# doodle_with_clock2_no_fil.net
KiCad netlist of a schematic drawn in EAGLE
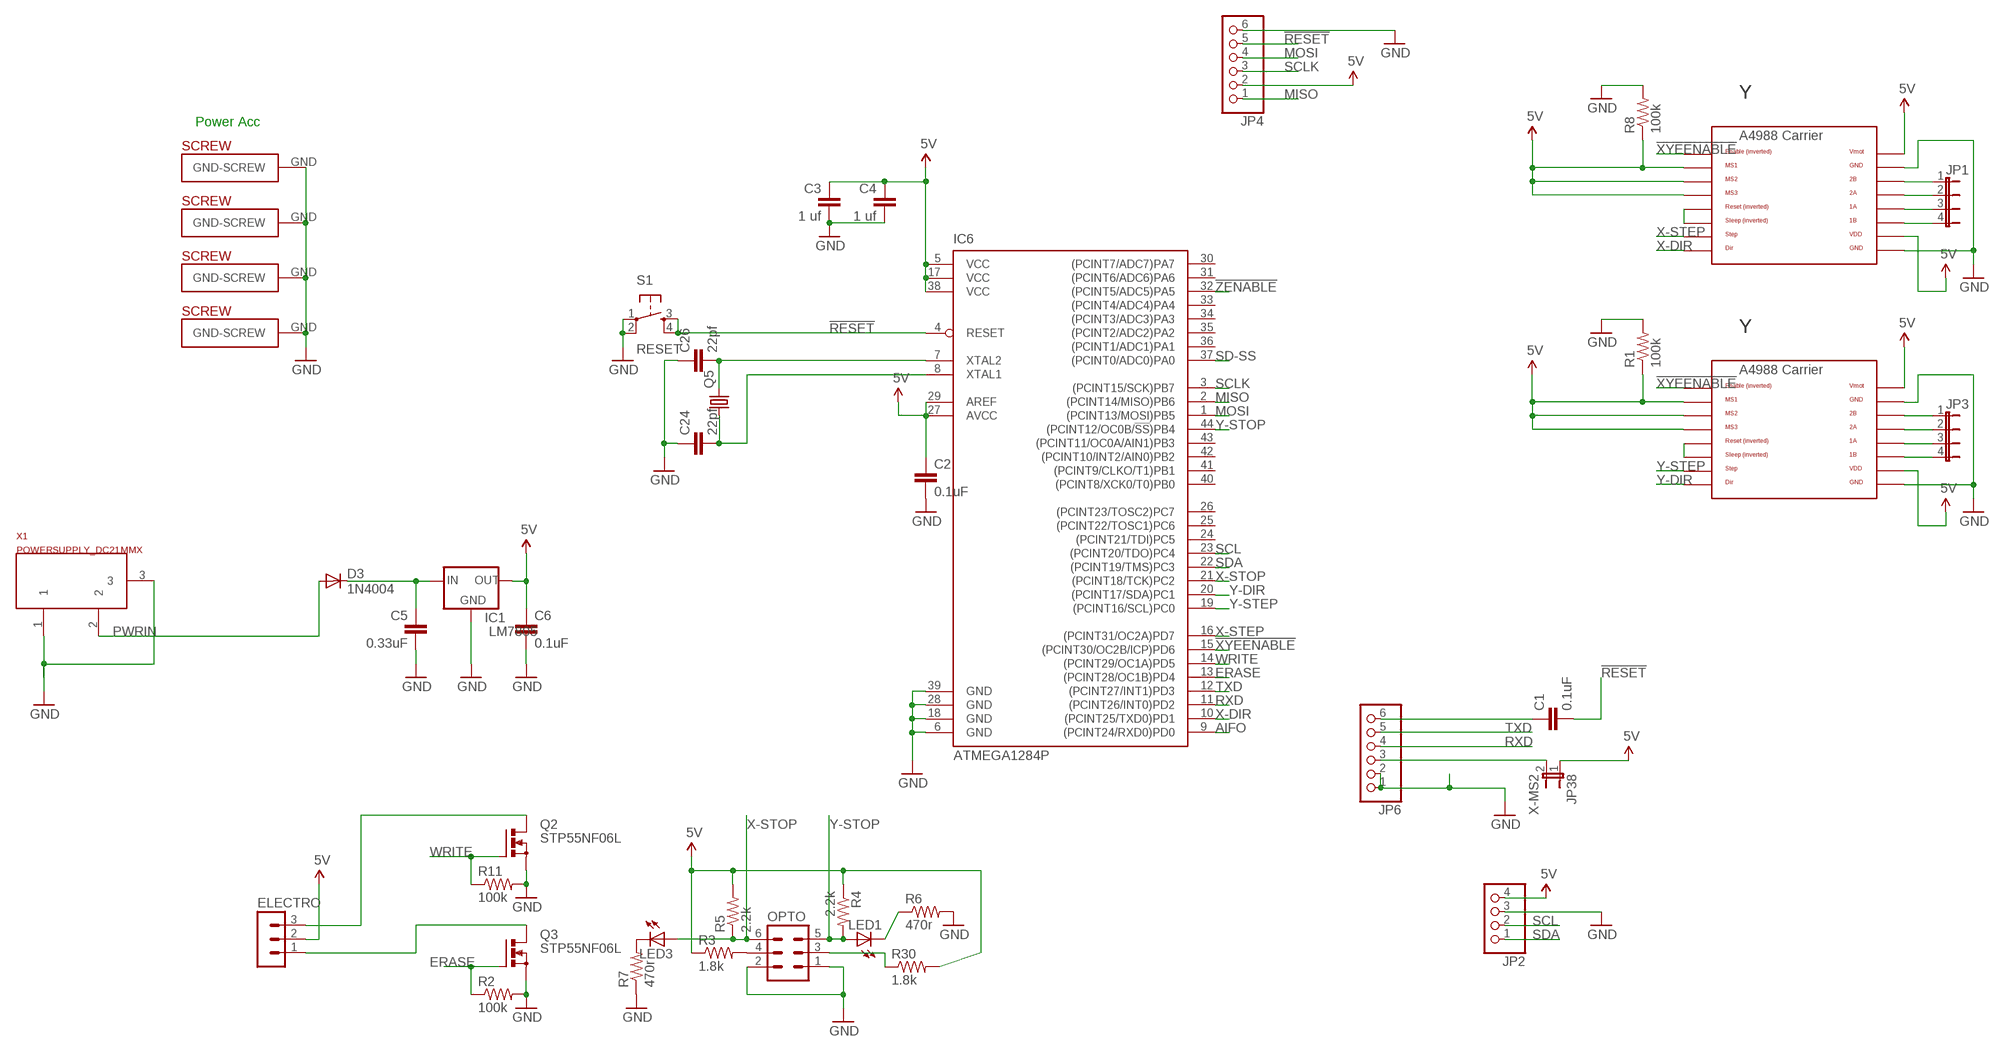
[diagram p0: schematic, sheet 1]

(export (version "E")
  (design (tool "Eeschema 10.0.6"))
  (components
    (comp (ref "C1")
      (value "0.1uF")
      (footprint "eagle-import:CAP-PTH-SMALL2")
      (libsource (lib "eagle-import") (part "CAPPTH2"))
    )
    (comp (ref "C2")
      (value "0.1uF")
      (footprint "eagle-import:CAP-PTH-SMALL2")
      (libsource (lib "eagle-import") (part "CAPPTH2"))
    )
    (comp (ref "C3")
      (value "1 uf")
      (footprint "eagle-import:CAP-PTH-SMALL2")
      (libsource (lib "eagle-import") (part "CAPPTH2"))
    )
    (comp (ref "C4")
      (value "1 uf")
      (footprint "eagle-import:CAP-PTH-SMALL2")
      (libsource (lib "eagle-import") (part "CAPPTH2"))
    )
    (comp (ref "C5")
      (value "0.33uF")
      (footprint "eagle-import:CAP-PTH-SMALL2")
      (libsource (lib "eagle-import") (part "CAPPTH2"))
    )
    (comp (ref "C6")
      (value "0.1uF")
      (footprint "eagle-import:CAP-PTH-SMALL2")
      (libsource (lib "eagle-import") (part "CAPPTH2"))
    )
    (comp (ref "C24")
      (value "22pf")
      (footprint "eagle-import:CAP-PTH-SMALL2")
      (libsource (lib "eagle-import") (part "CAPPTH2"))
    )
    (comp (ref "C26")
      (value "22pf")
      (footprint "eagle-import:CAP-PTH-SMALL2")
      (libsource (lib "eagle-import") (part "CAPPTH2"))
    )
    (comp (ref "D3")
      (value "1N4004")
      (footprint "eagle-import:DO41-10")
      (libsource (lib "eagle-import") (part "1N4004"))
    )
    (comp (ref "ELECTRO")
      (value "MA03-1")
      (footprint "eagle-import:MA03-1")
      (libsource (lib "eagle-import") (part "MA03-1"))
    )
    (comp (ref "IC1")
      (value "LM7805")
      (footprint "eagle-import:78XXL-CUSTOM")
      (libsource (lib "eagle-import") (part "V_REG_78XX"))
    )
    (comp (ref "IC6")
      (value "ATMEGA1284P")
      (footprint "eagle-import:TQFP44")
      (fields (field (name "MPN") "ATMEGA644PV-10AU"))
      (libsource (lib "eagle-import") (part "ATMEGA644A"))
    )
    (comp (ref "JP1")
      (value "JP4E")
      (footprint "eagle-import:JP4")
      (libsource (lib "eagle-import") (part "JP4E"))
    )
    (comp (ref "JP2")
      (value "PINHD-1X4")
      (footprint "eagle-import:1X04")
      (libsource (lib "eagle-import") (part "PINHD-1X4"))
    )
    (comp (ref "JP3")
      (value "JP4E")
      (footprint "eagle-import:JP4")
      (libsource (lib "eagle-import") (part "JP4E"))
    )
    (comp (ref "JP4")
      (value "PINHD-1X6/90")
      (footprint "eagle-import:1X06_90")
      (libsource (lib "eagle-import") (part "PINHD-1X6/90"))
    )
    (comp (ref "JP6")
      (value "PINHD-1X6")
      (footprint "eagle-import:1X06")
      (libsource (lib "eagle-import") (part "PINHD-1X6"))
    )
    (comp (ref "JP38")
      (value "X-MS2")
      (footprint "eagle-import:1X02")
      (libsource (lib "eagle-import") (part "JUMPER-2PTH"))
    )
    (comp (ref "LED1")
      (value "LED3MM")
      (footprint "eagle-import:LED3MM")
      (libsource (lib "eagle-import") (part "LED3MM"))
    )
    (comp (ref "LED3")
      (value "LED3MM")
      (footprint "eagle-import:LED3MM")
      (libsource (lib "eagle-import") (part "LED3MM"))
    )
    (comp (ref "OPTO")
      (value "MA03-2")
      (footprint "eagle-import:MA03-2")
      (libsource (lib "eagle-import") (part "MA03-2"))
    )
    (comp (ref "Q2")
      (value "STP55NF06L")
      (footprint "eagle-import:TO220BV")
      (libsource (lib "eagle-import") (part "IRF512"))
    )
    (comp (ref "Q3")
      (value "STP55NF06L")
      (footprint "eagle-import:TO220BV")
      (libsource (lib "eagle-import") (part "IRF512"))
    )
    (comp (ref "Q5")
      (value "CRYSTALHC49S")
      (footprint "eagle-import:HC49_S")
      (libsource (lib "eagle-import") (part "CRYSTALHC49S"))
    )
    (comp (ref "R1")
      (value "100k")
      (footprint "eagle-import:0207_7")
      (libsource (lib "eagle-import") (part "R-US_0207/7"))
    )
    (comp (ref "R2")
      (value "100k")
      (footprint "eagle-import:0207_2V")
      (libsource (lib "eagle-import") (part "resistor_R-US_0207/2V"))
    )
    (comp (ref "R3")
      (value "1.8k")
      (footprint "eagle-import:0207_2V")
      (libsource (lib "eagle-import") (part "resistor_R-US_0207/2V"))
    )
    (comp (ref "R4")
      (value "2.2k")
      (footprint "eagle-import:0207_2V")
      (libsource (lib "eagle-import") (part "resistor_R-US_0207/2V"))
    )
    (comp (ref "R5")
      (value "2.2k")
      (footprint "eagle-import:0207_2V")
      (libsource (lib "eagle-import") (part "resistor_R-US_0207/2V"))
    )
    (comp (ref "R6")
      (value "470r")
      (footprint "eagle-import:0207_2V")
      (libsource (lib "eagle-import") (part "resistor_R-US_0207/2V"))
    )
    (comp (ref "R7")
      (value "470r")
      (footprint "eagle-import:0207_2V")
      (libsource (lib "eagle-import") (part "resistor_R-US_0207/2V"))
    )
    (comp (ref "R8")
      (value "100k")
      (footprint "eagle-import:0207_7")
      (libsource (lib "eagle-import") (part "R-US_0207/7"))
    )
    (comp (ref "R11")
      (value "100k")
      (footprint "eagle-import:0207_2V")
      (libsource (lib "eagle-import") (part "resistor_R-US_0207/2V"))
    )
    (comp (ref "R30")
      (value "1.8k")
      (footprint "eagle-import:0207_2V")
      (libsource (lib "eagle-import") (part "resistor_R-US_0207/2V"))
    )
    (comp (ref "S1")
      (value "RESET")
      (footprint "eagle-import:TACTILE-PTH")
      (libsource (lib "eagle-import") (part "TAC_SWITCHPTH"))
    )
    (comp (ref "U$1")
      (value "A4988BREAKOUT")
      (footprint "eagle-import:A4988BREAKOUT")
      (libsource (lib "eagle-import") (part "A4988BREAKOUT"))
    )
    (comp (ref "U$7")
      (value "A4988BREAKOUT")
      (footprint "eagle-import:A4988BREAKOUT")
      (libsource (lib "eagle-import") (part "A4988BREAKOUT"))
    )
    (comp (ref "U$14")
      (value "PLATED-SCREW")
      (footprint "eagle-import:PLATEDSCREW")
      (libsource (lib "eagle-import") (part "PLATED-SCREW"))
    )
    (comp (ref "U$17")
      (value "PLATED-SCREW")
      (footprint "eagle-import:PLATEDSCREW")
      (libsource (lib "eagle-import") (part "PLATED-SCREW"))
    )
    (comp (ref "U$18")
      (value "PLATED-SCREW")
      (footprint "eagle-import:PLATEDSCREW")
      (libsource (lib "eagle-import") (part "PLATED-SCREW"))
    )
    (comp (ref "U$38")
      (value "PLATED-SCREW")
      (footprint "eagle-import:PLATEDSCREW")
      (libsource (lib "eagle-import") (part "PLATED-SCREW"))
    )
    (comp (ref "X1")
      (value "POWERSUPPLY_DC21MMX")
      (footprint "eagle-import:POWERSUPPLY_DC-21MM")
      (libsource (lib "eagle-import") (part "POWERSUPPLY_DC21MMX"))
    )
  )
  (nets
    (net (code "1") (name "/AIFO") (class "Default")
      (node (ref "IC6") (pin "9") (pinfunction "(PCINT24/RXD0)PD0_9") (pintype "bidirectional"))
    )
    (net (code "2") (name "/ERASE") (class "Default")
      (node (ref "IC6") (pin "13") (pinfunction "(PCINT28/OC1B)PD4_13") (pintype "bidirectional"))
      (node (ref "Q3") (pin "G") (pinfunction "G_G") (pintype "passive"))
      (node (ref "R2") (pin "1") (pinfunction "1_1") (pintype "passive"))
    )
    (net (code "3") (name "/MISO") (class "Default")
      (node (ref "IC6") (pin "2") (pinfunction "(PCINT14/MISO)PB6_2") (pintype "bidirectional"))
      (node (ref "JP4") (pin "1") (pinfunction "1_1") (pintype "passive"))
    )
    (net (code "4") (name "/MOSI") (class "Default")
      (node (ref "IC6") (pin "1") (pinfunction "(PCINT13/MOSI)PB5_1") (pintype "bidirectional"))
      (node (ref "JP4") (pin "4") (pinfunction "4_4") (pintype "passive"))
    )
    (net (code "5") (name "/PWRIN") (class "Default")
      (node (ref "D3") (pin "A") (pinfunction "A_A") (pintype "passive"))
      (node (ref "X1") (pin "2") (pinfunction "2_2") (pintype "power_in"))
    )
    (net (code "6") (name "/RXD") (class "Default")
      (node (ref "IC6") (pin "11") (pinfunction "(PCINT26/INT0)PD2_11") (pintype "bidirectional"))
      (node (ref "JP6") (pin "4") (pinfunction "4_4") (pintype "passive"))
    )
    (net (code "7") (name "/SCL") (class "Default")
      (node (ref "IC6") (pin "23") (pinfunction "(PCINT20/TDO)PC4_23") (pintype "output"))
      (node (ref "JP2") (pin "2") (pinfunction "2_2") (pintype "passive"))
    )
    (net (code "8") (name "/SCLK") (class "Default")
      (node (ref "IC6") (pin "3") (pinfunction "(PCINT15/SCK)PB7_3") (pintype "bidirectional"))
      (node (ref "JP4") (pin "3") (pinfunction "3_3") (pintype "passive"))
    )
    (net (code "9") (name "/SD-SS") (class "Default")
      (node (ref "IC6") (pin "37") (pinfunction "(PCINT0/ADC0)PA0_37") (pintype "bidirectional"))
    )
    (net (code "10") (name "/SDA") (class "Default")
      (node (ref "IC6") (pin "22") (pinfunction "(PCINT19/TMS)PC3_22") (pintype "output"))
      (node (ref "JP2") (pin "1") (pinfunction "1_1") (pintype "passive"))
    )
    (net (code "11") (name "/TXD") (class "Default")
      (node (ref "IC6") (pin "12") (pinfunction "(PCINT27/INT1)PD3_12") (pintype "bidirectional"))
      (node (ref "JP6") (pin "5") (pinfunction "5_5") (pintype "passive"))
    )
    (net (code "12") (name "/WRITE") (class "Default")
      (node (ref "IC6") (pin "14") (pinfunction "(PCINT29/OC1A)PD5_14") (pintype "bidirectional"))
      (node (ref "Q2") (pin "G") (pinfunction "G_G") (pintype "passive"))
      (node (ref "R11") (pin "1") (pinfunction "1_1") (pintype "passive"))
    )
    (net (code "13") (name "/X-DIR") (class "Default")
      (node (ref "IC6") (pin "10") (pinfunction "(PCINT25/TXD0)PD1_10") (pintype "bidirectional"))
      (node (ref "U$7") (pin "DIR") (pinfunction "DIR_DIR") (pintype "input"))
    )
    (net (code "14") (name "/X-STEP") (class "Default")
      (node (ref "IC6") (pin "16") (pinfunction "(PCINT31/OC2A)PD7_16") (pintype "bidirectional"))
      (node (ref "U$7") (pin "STEP") (pinfunction "STEP_STEP") (pintype "input"))
    )
    (net (code "15") (name "/X-STOP") (class "Default")
      (node (ref "IC6") (pin "21") (pinfunction "(PCINT18/TCK)PC2_21") (pintype "output"))
      (node (ref "LED3") (pin "A") (pinfunction "A_A") (pintype "passive"))
      (node (ref "OPTO") (pin "6") (pinfunction "6_6") (pintype "passive"))
      (node (ref "R5") (pin "1") (pinfunction "1_1") (pintype "passive"))
    )
    (net (code "16") (name "/Y-DIR") (class "Default")
      (node (ref "IC6") (pin "20") (pinfunction "(PCINT17/SDA)PC1_20") (pintype "output"))
      (node (ref "U$1") (pin "DIR") (pinfunction "DIR_DIR") (pintype "input"))
    )
    (net (code "17") (name "/Y-STEP") (class "Default")
      (node (ref "IC6") (pin "19") (pinfunction "(PCINT16/SCL)PC0_19") (pintype "output"))
      (node (ref "U$1") (pin "STEP") (pinfunction "STEP_STEP") (pintype "input"))
    )
    (net (code "18") (name "/Y-STOP") (class "Default")
      (node (ref "IC6") (pin "44") (pinfunction "(PCINT12/OC0B/~{SS})PB4_44") (pintype "bidirectional"))
      (node (ref "LED1") (pin "A") (pinfunction "A_A") (pintype "passive"))
      (node (ref "OPTO") (pin "5") (pinfunction "5_5") (pintype "passive"))
      (node (ref "R4") (pin "2") (pinfunction "2_2") (pintype "passive"))
    )
    (net (code "19") (name "/~{RESET}") (class "Default")
      (node (ref "C1") (pin "2") (pinfunction "2_2") (pintype "passive"))
      (node (ref "IC6") (pin "4") (pinfunction "RESET_4") (pintype "input"))
      (node (ref "JP4") (pin "5") (pinfunction "5_5") (pintype "passive"))
      (node (ref "S1") (pin "3") (pinfunction "3_3") (pintype "passive"))
      (node (ref "S1") (pin "4") (pinfunction "4_4") (pintype "passive"))
    )
    (net (code "20") (name "/~{XYEENABLE}") (class "Default")
      (node (ref "IC6") (pin "15") (pinfunction "(PCINT30/OC2B/ICP)PD6_15") (pintype "bidirectional"))
      (node (ref "U$1") (pin "EN") (pinfunction "EN_EN") (pintype "input"))
      (node (ref "U$7") (pin "EN") (pinfunction "EN_EN") (pintype "input"))
    )
    (net (code "21") (name "/~{ZENABLE}") (class "Default")
      (node (ref "IC6") (pin "32") (pinfunction "(PCINT5/ADC5)PA5_32") (pintype "bidirectional"))
    )
    (net (code "22") (name "5V") (class "Default")
      (node (ref "C2") (pin "1") (pinfunction "1_1") (pintype "passive"))
      (node (ref "C3") (pin "1") (pinfunction "1_1") (pintype "passive"))
      (node (ref "C4") (pin "1") (pinfunction "1_1") (pintype "passive"))
      (node (ref "C6") (pin "1") (pinfunction "1_1") (pintype "passive"))
      (node (ref "ELECTRO") (pin "2") (pinfunction "2_2") (pintype "passive"))
      (node (ref "IC1") (pin "OUT") (pinfunction "OUT_OUT") (pintype "output"))
      (node (ref "IC6") (pin "17") (pinfunction "VCC_17") (pintype "power_in"))
      (node (ref "IC6") (pin "27") (pinfunction "AVCC_27") (pintype "power_in"))
      (node (ref "IC6") (pin "29") (pinfunction "AREF_29") (pintype "passive"))
      (node (ref "IC6") (pin "38") (pinfunction "VCC_38") (pintype "power_in"))
      (node (ref "IC6") (pin "5") (pinfunction "VCC_5") (pintype "power_in"))
      (node (ref "JP2") (pin "4") (pinfunction "4_4") (pintype "passive"))
      (node (ref "JP38") (pin "1") (pinfunction "1_1") (pintype "passive"))
      (node (ref "JP4") (pin "2") (pinfunction "2_2") (pintype "passive"))
      (node (ref "R1") (pin "1") (pinfunction "1_1") (pintype "passive"))
      (node (ref "R3") (pin "1") (pinfunction "1_1") (pintype "passive"))
      (node (ref "R30") (pin "2") (pinfunction "2_2") (pintype "passive"))
      (node (ref "R4") (pin "1") (pinfunction "1_1") (pintype "passive"))
      (node (ref "R5") (pin "2") (pinfunction "2_2") (pintype "passive"))
      (node (ref "R8") (pin "1") (pinfunction "1_1") (pintype "passive"))
      (node (ref "U$1") (pin "MS1") (pinfunction "MS1_MS1") (pintype "input"))
      (node (ref "U$1") (pin "MS2") (pinfunction "MS2_MS2") (pintype "input"))
      (node (ref "U$1") (pin "MS3") (pinfunction "MS3_MS3") (pintype "input"))
      (node (ref "U$1") (pin "VDD") (pinfunction "VDD_VDD") (pintype "power_in"))
      (node (ref "U$1") (pin "VMOT") (pinfunction "VMOT_VMOT") (pintype "power_in"))
      (node (ref "U$7") (pin "MS1") (pinfunction "MS1_MS1") (pintype "input"))
      (node (ref "U$7") (pin "MS2") (pinfunction "MS2_MS2") (pintype "input"))
      (node (ref "U$7") (pin "MS3") (pinfunction "MS3_MS3") (pintype "input"))
      (node (ref "U$7") (pin "VDD") (pinfunction "VDD_VDD") (pintype "power_in"))
      (node (ref "U$7") (pin "VMOT") (pinfunction "VMOT_VMOT") (pintype "power_in"))
    )
    (net (code "23") (name "GND") (class "Default")
      (node (ref "C2") (pin "2") (pinfunction "2_2") (pintype "passive"))
      (node (ref "C24") (pin "1") (pinfunction "1_1") (pintype "passive"))
      (node (ref "C26") (pin "1") (pinfunction "1_1") (pintype "passive"))
      (node (ref "C3") (pin "2") (pinfunction "2_2") (pintype "passive"))
      (node (ref "C4") (pin "2") (pinfunction "2_2") (pintype "passive"))
      (node (ref "C5") (pin "2") (pinfunction "2_2") (pintype "passive"))
      (node (ref "C6") (pin "2") (pinfunction "2_2") (pintype "passive"))
      (node (ref "IC1") (pin "GND") (pinfunction "GND_GND") (pintype "input"))
      (node (ref "IC6") (pin "18") (pinfunction "GND_18") (pintype "power_in"))
      (node (ref "IC6") (pin "28") (pinfunction "GND_28") (pintype "power_in"))
      (node (ref "IC6") (pin "39") (pinfunction "GND_39") (pintype "power_in"))
      (node (ref "IC6") (pin "6") (pinfunction "GND_6") (pintype "power_in"))
      (node (ref "JP2") (pin "3") (pinfunction "3_3") (pintype "passive"))
      (node (ref "JP4") (pin "6") (pinfunction "6_6") (pintype "passive"))
      (node (ref "JP6") (pin "1") (pinfunction "1_1") (pintype "passive"))
      (node (ref "JP6") (pin "2") (pinfunction "2_2") (pintype "passive"))
      (node (ref "OPTO") (pin "1") (pinfunction "1_1") (pintype "passive"))
      (node (ref "OPTO") (pin "2") (pinfunction "2_2") (pintype "passive"))
      (node (ref "Q2") (pin "S") (pinfunction "S_S") (pintype "passive"))
      (node (ref "Q3") (pin "S") (pinfunction "S_S") (pintype "passive"))
      (node (ref "R1") (pin "2") (pinfunction "2_2") (pintype "passive"))
      (node (ref "R11") (pin "2") (pinfunction "2_2") (pintype "passive"))
      (node (ref "R2") (pin "2") (pinfunction "2_2") (pintype "passive"))
      (node (ref "R6") (pin "2") (pinfunction "2_2") (pintype "passive"))
      (node (ref "R7") (pin "1") (pinfunction "1_1") (pintype "passive"))
      (node (ref "R8") (pin "2") (pinfunction "2_2") (pintype "passive"))
      (node (ref "S1") (pin "1") (pinfunction "1_1") (pintype "passive"))
      (node (ref "S1") (pin "2") (pinfunction "2_2") (pintype "passive"))
      (node (ref "U$1") (pin "GND") (pinfunction "GND_GND") (pintype "power_in"))
      (node (ref "U$1") (pin "GND@0") (pinfunction "GND_GND@0") (pintype "power_in"))
      (node (ref "U$14") (pin "GND") (pinfunction "GND-SCREW_GND") (pintype "bidirectional"))
      (node (ref "U$17") (pin "GND") (pinfunction "GND-SCREW_GND") (pintype "bidirectional"))
      (node (ref "U$18") (pin "GND") (pinfunction "GND-SCREW_GND") (pintype "bidirectional"))
      (node (ref "U$38") (pin "GND") (pinfunction "GND-SCREW_GND") (pintype "bidirectional"))
      (node (ref "U$7") (pin "GND") (pinfunction "GND_GND") (pintype "power_in"))
      (node (ref "U$7") (pin "GND@0") (pinfunction "GND_GND@0") (pintype "power_in"))
      (node (ref "X1") (pin "1") (pinfunction "1_1") (pintype "power_in"))
      (node (ref "X1") (pin "3") (pinfunction "3_3") (pintype "power_in"))
    )
    (net (code "24") (name "Net-(C1-Pad1)") (class "Default")
      (node (ref "C1") (pin "1") (pinfunction "1_1") (pintype "passive"))
      (node (ref "JP6") (pin "6") (pinfunction "6_6") (pintype "passive"))
    )
    (net (code "25") (name "Net-(C5-Pad1)") (class "Default")
      (node (ref "C5") (pin "1") (pinfunction "1_1") (pintype "passive"))
      (node (ref "D3") (pin "C") (pinfunction "C_C") (pintype "passive"))
      (node (ref "IC1") (pin "IN") (pinfunction "IN_IN") (pintype "input"))
    )
    (net (code "26") (name "Net-(ELECTRO-Pad1)") (class "Default")
      (node (ref "ELECTRO") (pin "1") (pinfunction "1_1") (pintype "passive"))
      (node (ref "Q3") (pin "D") (pinfunction "D_D") (pintype "passive"))
    )
    (net (code "27") (name "Net-(ELECTRO-Pad3)") (class "Default")
      (node (ref "ELECTRO") (pin "3") (pinfunction "3_3") (pintype "passive"))
      (node (ref "Q2") (pin "D") (pinfunction "D_D") (pintype "passive"))
    )
    (net (code "28") (name "Net-(IC6-XTAL1)") (class "Default")
      (node (ref "C24") (pin "2") (pinfunction "2_2") (pintype "passive"))
      (node (ref "IC6") (pin "8") (pinfunction "XTAL1_8") (pintype "bidirectional"))
      (node (ref "Q5") (pin "1") (pinfunction "1_1") (pintype "passive"))
    )
    (net (code "29") (name "Net-(IC6-XTAL2)") (class "Default")
      (node (ref "C26") (pin "2") (pinfunction "2_2") (pintype "passive"))
      (node (ref "IC6") (pin "7") (pinfunction "XTAL2_7") (pintype "bidirectional"))
      (node (ref "Q5") (pin "2") (pinfunction "2_2") (pintype "passive"))
    )
    (net (code "30") (name "Net-(JP1-Pad1)") (class "Default")
      (node (ref "JP1") (pin "1") (pinfunction "1_1") (pintype "passive"))
      (node (ref "U$7") (pin "2B") (pinfunction "2B_2B") (pintype "output"))
    )
    (net (code "31") (name "Net-(JP1-Pad2)") (class "Default")
      (node (ref "JP1") (pin "2") (pinfunction "2_2") (pintype "passive"))
      (node (ref "U$7") (pin "2A") (pinfunction "2A_2A") (pintype "output"))
    )
    (net (code "32") (name "Net-(JP1-Pad3)") (class "Default")
      (node (ref "JP1") (pin "3") (pinfunction "3_3") (pintype "passive"))
      (node (ref "U$7") (pin "1A") (pinfunction "1A_1A") (pintype "output"))
    )
    (net (code "33") (name "Net-(JP1-Pad4)") (class "Default")
      (node (ref "JP1") (pin "4") (pinfunction "4_4") (pintype "passive"))
      (node (ref "U$7") (pin "1B") (pinfunction "1B_1B") (pintype "output"))
    )
    (net (code "34") (name "Net-(JP3-Pad1)") (class "Default")
      (node (ref "JP3") (pin "1") (pinfunction "1_1") (pintype "passive"))
      (node (ref "U$1") (pin "2B") (pinfunction "2B_2B") (pintype "output"))
    )
    (net (code "35") (name "Net-(JP3-Pad2)") (class "Default")
      (node (ref "JP3") (pin "2") (pinfunction "2_2") (pintype "passive"))
      (node (ref "U$1") (pin "2A") (pinfunction "2A_2A") (pintype "output"))
    )
    (net (code "36") (name "Net-(JP3-Pad3)") (class "Default")
      (node (ref "JP3") (pin "3") (pinfunction "3_3") (pintype "passive"))
      (node (ref "U$1") (pin "1A") (pinfunction "1A_1A") (pintype "output"))
    )
    (net (code "37") (name "Net-(JP3-Pad4)") (class "Default")
      (node (ref "JP3") (pin "4") (pinfunction "4_4") (pintype "passive"))
      (node (ref "U$1") (pin "1B") (pinfunction "1B_1B") (pintype "output"))
    )
    (net (code "38") (name "Net-(JP38-Pad2)") (class "Default")
      (node (ref "JP38") (pin "2") (pinfunction "2_2") (pintype "passive"))
      (node (ref "JP6") (pin "3") (pinfunction "3_3") (pintype "passive"))
    )
    (net (code "39") (name "Net-(LED1-C)") (class "Default")
      (node (ref "LED1") (pin "K") (pinfunction "C_K") (pintype "passive"))
      (node (ref "R6") (pin "1") (pinfunction "1_1") (pintype "passive"))
    )
    (net (code "40") (name "Net-(LED3-C)") (class "Default")
      (node (ref "LED3") (pin "K") (pinfunction "C_K") (pintype "passive"))
      (node (ref "R7") (pin "2") (pinfunction "2_2") (pintype "passive"))
    )
    (net (code "41") (name "Net-(OPTO-Pad3)") (class "Default")
      (node (ref "OPTO") (pin "3") (pinfunction "3_3") (pintype "passive"))
      (node (ref "R30") (pin "1") (pinfunction "1_1") (pintype "passive"))
    )
    (net (code "42") (name "Net-(OPTO-Pad4)") (class "Default")
      (node (ref "OPTO") (pin "4") (pinfunction "4_4") (pintype "passive"))
      (node (ref "R3") (pin "2") (pinfunction "2_2") (pintype "passive"))
    )
    (net (code "43") (name "Net-(U$1-SLEEP)") (class "Default")
      (node (ref "U$1") (pin "RST") (pinfunction "RST_RST") (pintype "input"))
      (node (ref "U$1") (pin "SLP") (pinfunction "SLEEP_SLP") (pintype "input"))
    )
    (net (code "44") (name "Net-(U$7-SLEEP)") (class "Default")
      (node (ref "U$7") (pin "RST") (pinfunction "RST_RST") (pintype "input"))
      (node (ref "U$7") (pin "SLP") (pinfunction "SLEEP_SLP") (pintype "input"))
    )
    (net (code "45") (name "unconnected-(IC6-(PCINT1{slash}ADC1)PA1-Pad36)") (class "Default")
      (node (ref "IC6") (pin "36") (pinfunction "(PCINT1/ADC1)PA1_36") (pintype "bidirectional"))
    )
    (net (code "46") (name "unconnected-(IC6-(PCINT2{slash}ADC2)PA2-Pad35)") (class "Default")
      (node (ref "IC6") (pin "35") (pinfunction "(PCINT2/ADC2)PA2_35") (pintype "bidirectional"))
    )
    (net (code "47") (name "unconnected-(IC6-(PCINT3{slash}ADC3)PA3-Pad34)") (class "Default")
      (node (ref "IC6") (pin "34") (pinfunction "(PCINT3/ADC3)PA3_34") (pintype "bidirectional"))
    )
    (net (code "48") (name "unconnected-(IC6-(PCINT4{slash}ADC4)PA4-Pad33)") (class "Default")
      (node (ref "IC6") (pin "33") (pinfunction "(PCINT4/ADC4)PA4_33") (pintype "bidirectional"))
    )
    (net (code "49") (name "unconnected-(IC6-(PCINT6{slash}ADC6)PA6-Pad31)") (class "Default")
      (node (ref "IC6") (pin "31") (pinfunction "(PCINT6/ADC6)PA6_31") (pintype "bidirectional"))
    )
    (net (code "50") (name "unconnected-(IC6-(PCINT7{slash}ADC7)PA7-Pad30)") (class "Default")
      (node (ref "IC6") (pin "30") (pinfunction "(PCINT7/ADC7)PA7_30") (pintype "bidirectional"))
    )
    (net (code "51") (name "unconnected-(IC6-(PCINT8{slash}XCK0{slash}T0)PB0-Pad40)") (class "Default")
      (node (ref "IC6") (pin "40") (pinfunction "(PCINT8/XCK0/T0)PB0_40") (pintype "bidirectional"))
    )
    (net (code "52") (name "unconnected-(IC6-(PCINT9{slash}CLKO{slash}T1)PB1-Pad41)") (class "Default")
      (node (ref "IC6") (pin "41") (pinfunction "(PCINT9/CLKO/T1)PB1_41") (pintype "bidirectional"))
    )
    (net (code "53") (name "unconnected-(IC6-(PCINT10{slash}INT2{slash}AIN0)PB2-Pad42)") (class "Default")
      (node (ref "IC6") (pin "42") (pinfunction "(PCINT10/INT2/AIN0)PB2_42") (pintype "bidirectional"))
    )
    (net (code "54") (name "unconnected-(IC6-(PCINT11{slash}OC0A{slash}AIN1)PB3-Pad43)") (class "Default")
      (node (ref "IC6") (pin "43") (pinfunction "(PCINT11/OC0A/AIN1)PB3_43") (pintype "bidirectional"))
    )
    (net (code "55") (name "unconnected-(IC6-(PCINT21{slash}TDI)PC5-Pad24)") (class "Default")
      (node (ref "IC6") (pin "24") (pinfunction "(PCINT21/TDI)PC5_24") (pintype "output"))
    )
    (net (code "56") (name "unconnected-(IC6-(PCINT22{slash}TOSC1)PC6-Pad25)") (class "Default")
      (node (ref "IC6") (pin "25") (pinfunction "(PCINT22/TOSC1)PC6_25") (pintype "output"))
    )
    (net (code "57") (name "unconnected-(IC6-(PCINT23{slash}TOSC2)PC7-Pad26)") (class "Default")
      (node (ref "IC6") (pin "26") (pinfunction "(PCINT23/TOSC2)PC7_26") (pintype "output"))
    )
  )
)
